# 7474-strobe-generator-v3a.net
KiCad netlist of a schematic drawn in EAGLE
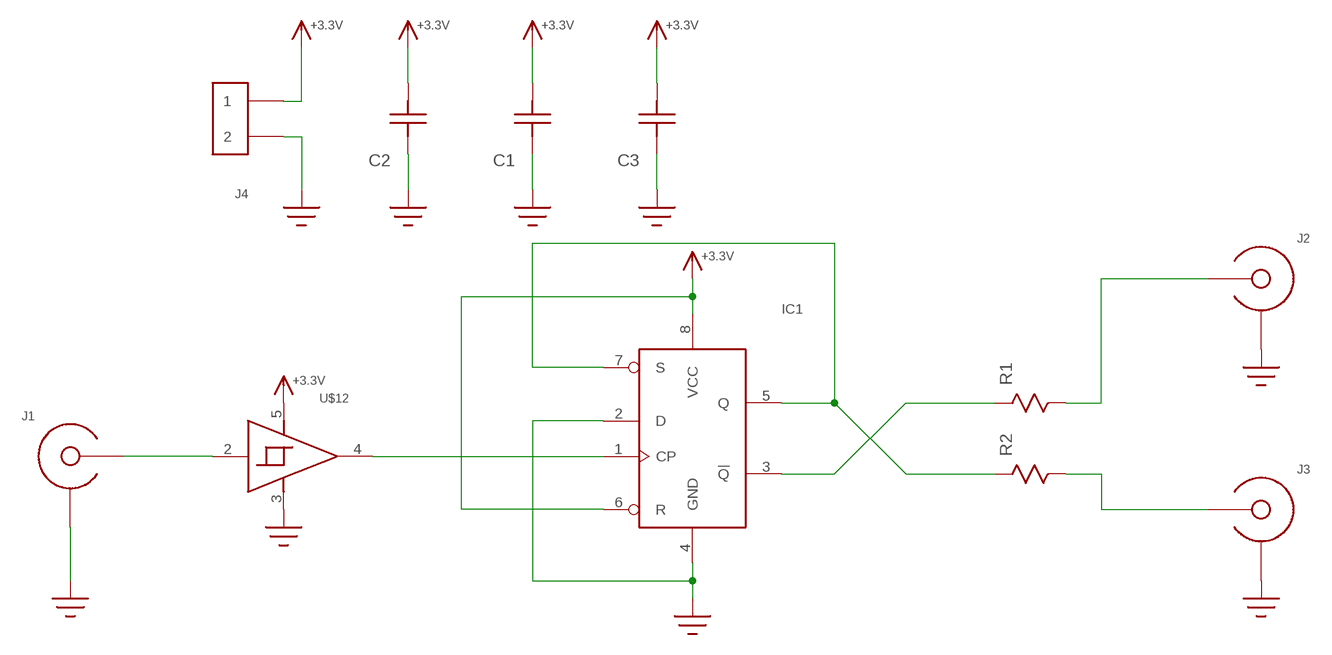
[diagram p0: schematic, sheet 1]

(export (version "E")
  (design (tool "Eeschema 10.0.6"))
  (components
    (comp (ref "C1")
      (value "C0603")
      (footprint "eagle-import:C0603")
      (libsource (lib "eagle-import") (part "C0603"))
    )
    (comp (ref "C2")
      (value "C1206")
      (footprint "eagle-import:1206")
      (libsource (lib "eagle-import") (part "C1206"))
    )
    (comp (ref "C3")
      (value "C0603")
      (footprint "eagle-import:C0603")
      (libsource (lib "eagle-import") (part "C0603"))
    )
    (comp (ref "IC1")
      (value "74LVC2G74")
      (footprint "eagle-import:SSOP8")
      (libsource (lib "eagle-import") (part "74LVC2G74"))
    )
    (comp (ref "J1")
      (value "SMA-EDGE-LAUNCH4020_TAPER")
      (footprint "eagle-import:SMA_EDGE_LAUNCH_2L_4020_TAPER")
      (libsource (lib "eagle-import") (part "SMA-EDGE-LAUNCH4020_TAPER"))
    )
    (comp (ref "J2")
      (value "SMA-EDGE-LAUNCH4020_TAPER")
      (footprint "eagle-import:SMA_EDGE_LAUNCH_2L_4020_TAPER")
      (libsource (lib "eagle-import") (part "SMA-EDGE-LAUNCH4020_TAPER"))
    )
    (comp (ref "J3")
      (value "SMA-EDGE-LAUNCH4020_TAPER")
      (footprint "eagle-import:SMA_EDGE_LAUNCH_2L_4020_TAPER")
      (libsource (lib "eagle-import") (part "SMA-EDGE-LAUNCH4020_TAPER"))
    )
    (comp (ref "J4")
      (value "HEADER_2PIN")
      (footprint "eagle-import:HEADER_2PIN")
      (libsource (lib "eagle-import") (part "HEADER_2PIN"))
    )
    (comp (ref "R1")
      (value "R0603")
      (footprint "eagle-import:R0603")
      (libsource (lib "eagle-import") (part "R0603"))
    )
    (comp (ref "R2")
      (value "R0603")
      (footprint "eagle-import:R0603")
      (libsource (lib "eagle-import") (part "R0603"))
    )
    (comp (ref "U$12")
      (value "74LVC1G17")
      (footprint "eagle-import:SOT23-5")
      (libsource (lib "eagle-import") (part "74LVC1G17"))
    )
  )
  (nets
    (net (code "1") (name "+3.3V") (class "Default")
      (node (ref "C1") (pin "P$1") (pinfunction "P$1_P$1") (pintype "bidirectional"))
      (node (ref "C2") (pin "P$1") (pinfunction "P$1_P$1") (pintype "bidirectional"))
      (node (ref "C3") (pin "P$1") (pinfunction "P$1_P$1") (pintype "bidirectional"))
      (node (ref "IC1") (pin "6") (pinfunction "R_6") (pintype "bidirectional"))
      (node (ref "IC1") (pin "8") (pinfunction "VCC_8") (pintype "bidirectional"))
      (node (ref "J4") (pin "1") (pinfunction "1_1") (pintype "bidirectional"))
      (node (ref "U$12") (pin "5") (pinfunction "VCC_5") (pintype "bidirectional"))
    )
    (net (code "2") (name "GND") (class "Default")
      (node (ref "C1") (pin "P$2") (pinfunction "P$2_P$2") (pintype "bidirectional"))
      (node (ref "C2") (pin "P$2") (pinfunction "P$2_P$2") (pintype "bidirectional"))
      (node (ref "C3") (pin "P$2") (pinfunction "P$2_P$2") (pintype "bidirectional"))
      (node (ref "IC1") (pin "2") (pinfunction "D_2") (pintype "bidirectional"))
      (node (ref "IC1") (pin "4") (pinfunction "GND_4") (pintype "bidirectional"))
      (node (ref "J1") (pin "BOTTOM_GND") (pinfunction "SHIELD_BOTTOM_GND") (pintype "bidirectional"))
      (node (ref "J1") (pin "GND@1") (pinfunction "SHIELD_GND@1") (pintype "bidirectional"))
      (node (ref "J1") (pin "GND@14") (pinfunction "SHIELD_GND@14") (pintype "bidirectional"))
      (node (ref "J1") (pin "GND@15") (pinfunction "SHIELD_GND@15") (pintype "bidirectional"))
      (node (ref "J1") (pin "GND@16") (pinfunction "SHIELD_GND@16") (pintype "bidirectional"))
      (node (ref "J1") (pin "GND@17") (pinfunction "SHIELD_GND@17") (pintype "bidirectional"))
      (node (ref "J1") (pin "GND@2") (pinfunction "SHIELD_GND@2") (pintype "bidirectional"))
      (node (ref "J1") (pin "GND@3") (pinfunction "SHIELD_GND@3") (pintype "bidirectional"))
      (node (ref "J1") (pin "GND@4") (pinfunction "SHIELD_GND@4") (pintype "bidirectional"))
      (node (ref "J1") (pin "GND@5") (pinfunction "SHIELD_GND@5") (pintype "bidirectional"))
      (node (ref "J1") (pin "GND@6") (pinfunction "SHIELD_GND@6") (pintype "bidirectional"))
      (node (ref "J1") (pin "GND@7") (pinfunction "SHIELD_GND@7") (pintype "bidirectional"))
      (node (ref "J1") (pin "GND@8") (pinfunction "SHIELD_GND@8") (pintype "bidirectional"))
      (node (ref "J1") (pin "GND_PAD1") (pinfunction "SHIELD_GND_PAD1") (pintype "bidirectional"))
      (node (ref "J1") (pin "GND_PAD2") (pinfunction "SHIELD_GND_PAD2") (pintype "bidirectional"))
      (node (ref "J1") (pin "P$1") (pinfunction "SHIELD_P$1") (pintype "bidirectional"))
      (node (ref "J1") (pin "P$2") (pinfunction "SHIELD_P$2") (pintype "bidirectional"))
      (node (ref "J2") (pin "BOTTOM_GND") (pinfunction "SHIELD_BOTTOM_GND") (pintype "bidirectional"))
      (node (ref "J2") (pin "GND@1") (pinfunction "SHIELD_GND@1") (pintype "bidirectional"))
      (node (ref "J2") (pin "GND@14") (pinfunction "SHIELD_GND@14") (pintype "bidirectional"))
      (node (ref "J2") (pin "GND@15") (pinfunction "SHIELD_GND@15") (pintype "bidirectional"))
      (node (ref "J2") (pin "GND@16") (pinfunction "SHIELD_GND@16") (pintype "bidirectional"))
      (node (ref "J2") (pin "GND@17") (pinfunction "SHIELD_GND@17") (pintype "bidirectional"))
      (node (ref "J2") (pin "GND@2") (pinfunction "SHIELD_GND@2") (pintype "bidirectional"))
      (node (ref "J2") (pin "GND@3") (pinfunction "SHIELD_GND@3") (pintype "bidirectional"))
      (node (ref "J2") (pin "GND@4") (pinfunction "SHIELD_GND@4") (pintype "bidirectional"))
      (node (ref "J2") (pin "GND@5") (pinfunction "SHIELD_GND@5") (pintype "bidirectional"))
      (node (ref "J2") (pin "GND@6") (pinfunction "SHIELD_GND@6") (pintype "bidirectional"))
      (node (ref "J2") (pin "GND@7") (pinfunction "SHIELD_GND@7") (pintype "bidirectional"))
      (node (ref "J2") (pin "GND@8") (pinfunction "SHIELD_GND@8") (pintype "bidirectional"))
      (node (ref "J2") (pin "GND_PAD1") (pinfunction "SHIELD_GND_PAD1") (pintype "bidirectional"))
      (node (ref "J2") (pin "GND_PAD2") (pinfunction "SHIELD_GND_PAD2") (pintype "bidirectional"))
      (node (ref "J2") (pin "P$1") (pinfunction "SHIELD_P$1") (pintype "bidirectional"))
      (node (ref "J2") (pin "P$2") (pinfunction "SHIELD_P$2") (pintype "bidirectional"))
      (node (ref "J3") (pin "BOTTOM_GND") (pinfunction "SHIELD_BOTTOM_GND") (pintype "bidirectional"))
      (node (ref "J3") (pin "GND@1") (pinfunction "SHIELD_GND@1") (pintype "bidirectional"))
      (node (ref "J3") (pin "GND@14") (pinfunction "SHIELD_GND@14") (pintype "bidirectional"))
      (node (ref "J3") (pin "GND@15") (pinfunction "SHIELD_GND@15") (pintype "bidirectional"))
      (node (ref "J3") (pin "GND@16") (pinfunction "SHIELD_GND@16") (pintype "bidirectional"))
      (node (ref "J3") (pin "GND@17") (pinfunction "SHIELD_GND@17") (pintype "bidirectional"))
      (node (ref "J3") (pin "GND@2") (pinfunction "SHIELD_GND@2") (pintype "bidirectional"))
      (node (ref "J3") (pin "GND@3") (pinfunction "SHIELD_GND@3") (pintype "bidirectional"))
      (node (ref "J3") (pin "GND@4") (pinfunction "SHIELD_GND@4") (pintype "bidirectional"))
      (node (ref "J3") (pin "GND@5") (pinfunction "SHIELD_GND@5") (pintype "bidirectional"))
      (node (ref "J3") (pin "GND@6") (pinfunction "SHIELD_GND@6") (pintype "bidirectional"))
      (node (ref "J3") (pin "GND@7") (pinfunction "SHIELD_GND@7") (pintype "bidirectional"))
      (node (ref "J3") (pin "GND@8") (pinfunction "SHIELD_GND@8") (pintype "bidirectional"))
      (node (ref "J3") (pin "GND_PAD1") (pinfunction "SHIELD_GND_PAD1") (pintype "bidirectional"))
      (node (ref "J3") (pin "GND_PAD2") (pinfunction "SHIELD_GND_PAD2") (pintype "bidirectional"))
      (node (ref "J3") (pin "P$1") (pinfunction "SHIELD_P$1") (pintype "bidirectional"))
      (node (ref "J3") (pin "P$2") (pinfunction "SHIELD_P$2") (pintype "bidirectional"))
      (node (ref "J4") (pin "2") (pinfunction "2_2") (pintype "bidirectional"))
      (node (ref "U$12") (pin "3") (pinfunction "GND_3") (pintype "bidirectional"))
    )
    (net (code "3") (name "Net-(IC1-CP)") (class "Default")
      (node (ref "IC1") (pin "1") (pinfunction "CP_1") (pintype "bidirectional"))
      (node (ref "U$12") (pin "4") (pinfunction "OUT_4") (pintype "bidirectional"))
    )
    (net (code "4") (name "Net-(IC1-Q)") (class "Default")
      (node (ref "IC1") (pin "5") (pinfunction "Q_5") (pintype "bidirectional"))
      (node (ref "IC1") (pin "7") (pinfunction "S_7") (pintype "bidirectional"))
      (node (ref "R2") (pin "P$1") (pinfunction "P$3_P$1") (pintype "bidirectional"))
    )
    (net (code "5") (name "Net-(IC1-~{Q})") (class "Default")
      (node (ref "IC1") (pin "3") (pinfunction "~{Q}_3") (pintype "bidirectional"))
      (node (ref "R1") (pin "P$1") (pinfunction "P$3_P$1") (pintype "bidirectional"))
    )
    (net (code "6") (name "Net-(J1-CENTER)") (class "Default")
      (node (ref "J1") (pin "CENTER@1") (pinfunction "CENTER_CENTER@1") (pintype "bidirectional"))
      (node (ref "U$12") (pin "2") (pinfunction "IN_2") (pintype "bidirectional"))
    )
    (net (code "7") (name "Net-(J2-CENTER)") (class "Default")
      (node (ref "J2") (pin "CENTER@1") (pinfunction "CENTER_CENTER@1") (pintype "bidirectional"))
      (node (ref "R1") (pin "P$2") (pinfunction "P$4_P$2") (pintype "bidirectional"))
    )
    (net (code "8") (name "Net-(J3-CENTER)") (class "Default")
      (node (ref "J3") (pin "CENTER@1") (pinfunction "CENTER_CENTER@1") (pintype "bidirectional"))
      (node (ref "R2") (pin "P$2") (pinfunction "P$4_P$2") (pintype "bidirectional"))
    )
  )
)
